# mcu.net
KiCad netlist of a schematic drawn in Altium Designer
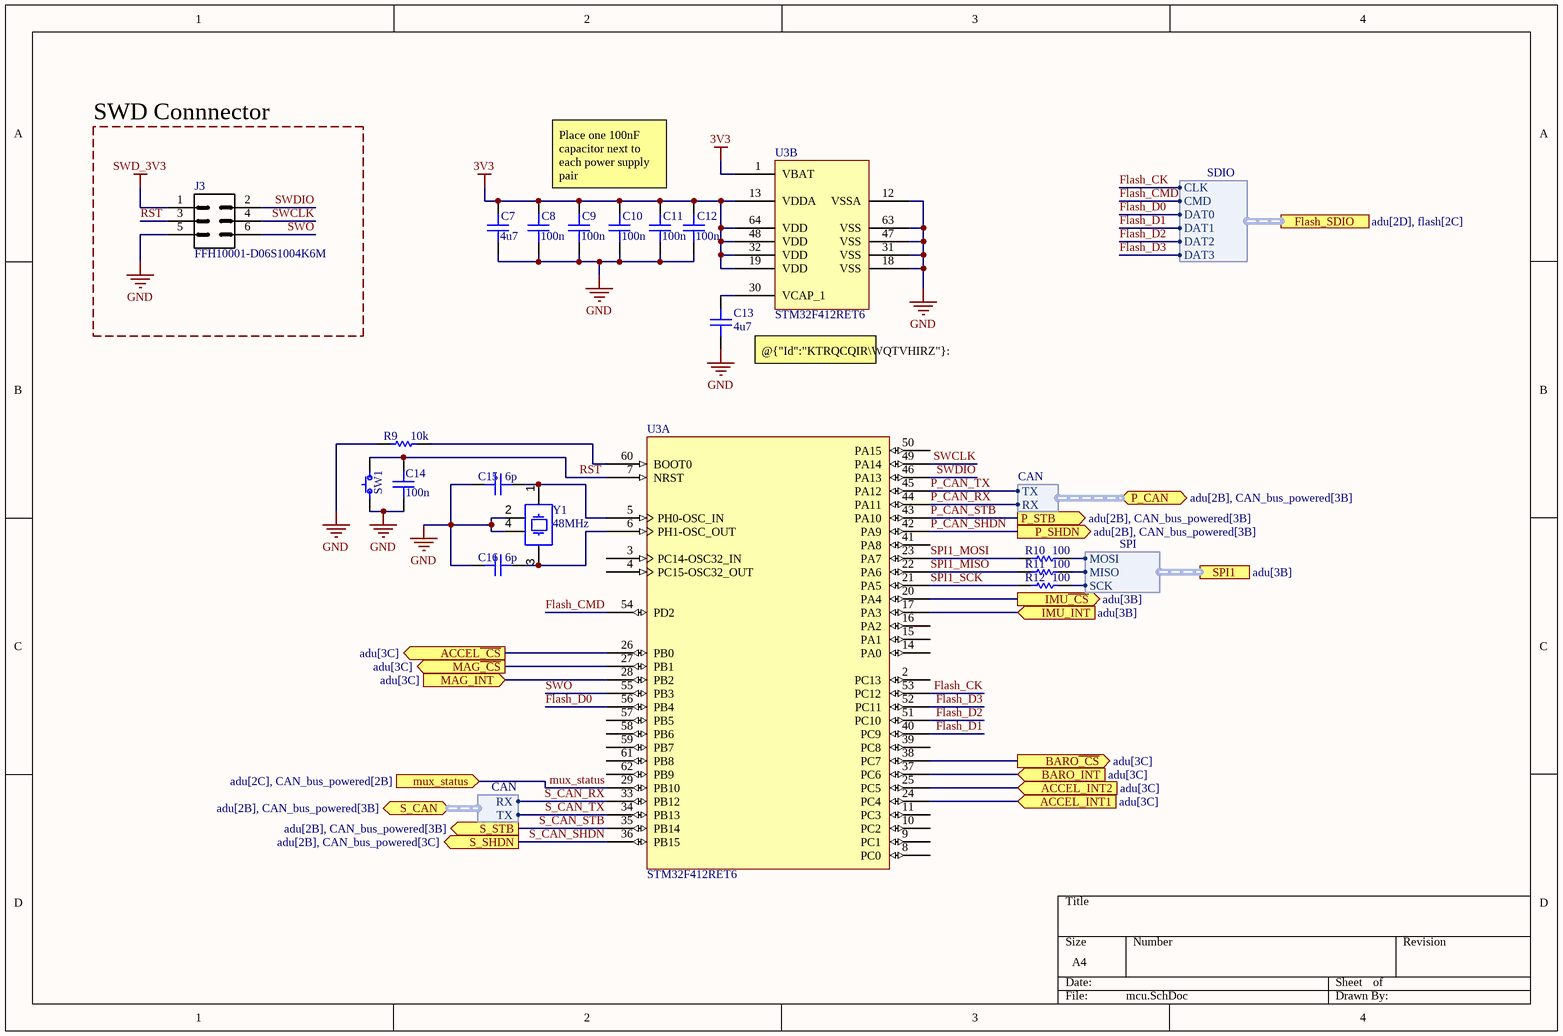
[diagram p0: mcu.SchDoc]

(export (version "E")
  (design (tool "Eeschema 10.0.6"))
  (components
    (comp (ref "C7")
      (value "4u7")
      (footprint "CAP-0603-NP")
      (description "Capacitor")
      (libsource (lib "drfc_schlib") (part "Capacitor"))
    )
    (comp (ref "C8")
      (value "100n")
      (footprint "CAP-0603-NP")
      (description "Capacitor")
      (libsource (lib "drfc_schlib") (part "Capacitor"))
    )
    (comp (ref "C9")
      (value "100n")
      (footprint "CAP-0603-NP")
      (description "Capacitor")
      (libsource (lib "drfc_schlib") (part "Capacitor"))
    )
    (comp (ref "C10")
      (value "100n")
      (footprint "CAP-0603-NP")
      (description "Capacitor")
      (libsource (lib "drfc_schlib") (part "Capacitor"))
    )
    (comp (ref "C11")
      (value "100n")
      (footprint "CAP-0603-NP")
      (description "Capacitor")
      (libsource (lib "drfc_schlib") (part "Capacitor"))
    )
    (comp (ref "C12")
      (value "100n")
      (footprint "CAP-0603-NP")
      (description "Capacitor")
      (libsource (lib "drfc_schlib") (part "Capacitor"))
    )
    (comp (ref "C13")
      (value "4u7")
      (footprint "CAP-0603-NP")
      (description "Capacitor")
      (libsource (lib "drfc_schlib") (part "Capacitor"))
    )
    (comp (ref "C14")
      (value "100n")
      (footprint "CAP-0603-NP")
      (description "Capacitor")
      (libsource (lib "drfc_schlib") (part "Capacitor"))
    )
    (comp (ref "C15")
      (value "6p")
      (footprint "CAP-0603-NP")
      (description "Capacitor")
      (libsource (lib "drfc_schlib") (part "Capacitor"))
    )
    (comp (ref "C16")
      (value "6p")
      (footprint "CAP-0603-NP")
      (description "Capacitor")
      (libsource (lib "drfc_schlib") (part "Capacitor"))
    )
    (comp (ref "J3")
      (value "FFH10001-D06S1004K6M")
      (footprint "SOP127P600-8N")
      (description "Connector 6-Pin 2 Row")
      (libsource (lib "drfc_schlib") (part "Connector 6-Pin 2 Row"))
    )
    (comp (ref "R9")
      (value "10k")
      (footprint "RES-0603")
      (description "Resistor")
      (libsource (lib "drfc_schlib") (part "Resistor"))
    )
    (comp (ref "R10")
      (value "100")
      (footprint "RES-0603")
      (description "Resistor")
      (libsource (lib "drfc_schlib") (part "Resistor"))
    )
    (comp (ref "R11")
      (value "100")
      (footprint "RES-0603")
      (description "Resistor")
      (libsource (lib "drfc_schlib") (part "Resistor"))
    )
    (comp (ref "R12")
      (value "100")
      (footprint "RES-0603")
      (description "Resistor")
      (libsource (lib "drfc_schlib") (part "Resistor"))
    )
    (comp (ref "SW1")
      (value "SPST Switch")
      (footprint "HYP 1TS026A-1000-0550-CT")
      (description "HYP (Hongyuan Precision) 1TS026A-1000-0550-CT")
      (libsource (lib "drfc_schlib") (part "SW_SPST"))
    )
    (comp (ref "U3")
      (value "STM32F412RET6")
      (footprint "STM32 LQFP64")
      (libsource (lib "drfc_schlib") (part "STM32F412RET6"))
    )
    (comp (ref "Y1")
      (value "48MHz")
      (footprint "XTAL_3.2x2.5mm")
      (description "HCI XC32M4-48.000-F08NLDT\r\n8pF load capacitance")
      (libsource (lib "drfc_schlib") (part "XTAL-4Pin"))
    )
  )
  (nets
    (net (code "4") (name "/ACCEL_INT1") (class "Default")
      (node (ref "U3") (pin "24") (pinfunction "PC4_24") (pintype "bidirectional"))
    )
    (net (code "5") (name "/ACCEL_INT2") (class "Default")
      (node (ref "U3") (pin "25") (pinfunction "PC5_25") (pintype "bidirectional"))
    )
    (net (code "6") (name "/ACCEL~{_CS}") (class "Default")
      (node (ref "U3") (pin "26") (pinfunction "PB0_26") (pintype "bidirectional"))
    )
    (net (code "7") (name "/BARO_INT") (class "Default")
      (node (ref "U3") (pin "37") (pinfunction "PC6_37") (pintype "bidirectional"))
    )
    (net (code "8") (name "/BARO~{_CS}") (class "Default")
      (node (ref "U3") (pin "38") (pinfunction "PC7_38") (pintype "bidirectional"))
    )
    (net (code "9") (name "/Flash_CK") (class "Default")
      (node (ref "U3") (pin "53") (pinfunction "PC12_53") (pintype "bidirectional"))
    )
    (net (code "10") (name "/Flash_CMD") (class "Default")
      (node (ref "U3") (pin "54") (pinfunction "PD2_54") (pintype "bidirectional"))
    )
    (net (code "11") (name "/Flash_D0") (class "Default")
      (node (ref "U3") (pin "56") (pinfunction "PB4_56") (pintype "bidirectional"))
    )
    (net (code "12") (name "/Flash_D1") (class "Default")
      (node (ref "U3") (pin "40") (pinfunction "PC9_40") (pintype "bidirectional"))
    )
    (net (code "13") (name "/Flash_D2") (class "Default")
      (node (ref "U3") (pin "51") (pinfunction "PC10_51") (pintype "bidirectional"))
    )
    (net (code "14") (name "/Flash_D3") (class "Default")
      (node (ref "U3") (pin "52") (pinfunction "PC11_52") (pintype "bidirectional"))
    )
    (net (code "15") (name "/IMU_INT") (class "Default")
      (node (ref "U3") (pin "17") (pinfunction "PA3_17") (pintype "bidirectional"))
    )
    (net (code "16") (name "/IMU~{_CS}") (class "Default")
      (node (ref "U3") (pin "20") (pinfunction "PA4_20") (pintype "bidirectional"))
    )
    (net (code "17") (name "/MAG_INT") (class "Default")
      (node (ref "U3") (pin "28") (pinfunction "PB2_28") (pintype "bidirectional"))
    )
    (net (code "18") (name "/MAG~{_CS}") (class "Default")
      (node (ref "U3") (pin "27") (pinfunction "PB1_27") (pintype "bidirectional"))
    )
    (net (code "19") (name "/MISO") (class "Default")
      (node (ref "R11") (pin "1") (pinfunction "1_1") (pintype "passive"))
    )
    (net (code "20") (name "/MOSI") (class "Default")
      (node (ref "R10") (pin "1") (pinfunction "1_1") (pintype "passive"))
    )
    (net (code "21") (name "/P_CAN_RX") (class "Default")
      (node (ref "U3") (pin "44") (pinfunction "PA11_44") (pintype "bidirectional"))
    )
    (net (code "22") (name "/P_CAN_SHDN") (class "Default")
      (node (ref "U3") (pin "42") (pinfunction "PA9_42") (pintype "bidirectional"))
    )
    (net (code "23") (name "/P_CAN_STB") (class "Default")
      (node (ref "U3") (pin "43") (pinfunction "PA10_43") (pintype "bidirectional"))
    )
    (net (code "24") (name "/P_CAN_TX") (class "Default")
      (node (ref "U3") (pin "45") (pinfunction "PA12_45") (pintype "bidirectional"))
    )
    (net (code "25") (name "/RST") (class "Default")
      (node (ref "C14") (pin "2") (pinfunction "2_2") (pintype "passive"))
      (node (ref "J3") (pin "3") (pinfunction "3_3") (pintype "passive"))
      (node (ref "SW1") (pin "2") (pinfunction "2_2") (pintype "passive"))
      (node (ref "U3") (pin "7") (pinfunction "NRST_7") (pintype "input"))
    )
    (net (code "26") (name "/SCK") (class "Default")
      (node (ref "R12") (pin "1") (pinfunction "1_1") (pintype "passive"))
    )
    (net (code "27") (name "/SPI1_MISO") (class "Default")
      (node (ref "R11") (pin "2") (pinfunction "2_2") (pintype "passive"))
      (node (ref "U3") (pin "22") (pinfunction "PA6_22") (pintype "bidirectional"))
    )
    (net (code "28") (name "/SPI1_MOSI") (class "Default")
      (node (ref "R10") (pin "2") (pinfunction "2_2") (pintype "passive"))
      (node (ref "U3") (pin "23") (pinfunction "PA7_23") (pintype "bidirectional"))
    )
    (net (code "29") (name "/SPI1_SCK") (class "Default")
      (node (ref "R12") (pin "2") (pinfunction "2_2") (pintype "passive"))
      (node (ref "U3") (pin "21") (pinfunction "PA5_21") (pintype "bidirectional"))
    )
    (net (code "30") (name "/SWCLK") (class "Default")
      (node (ref "J3") (pin "4") (pinfunction "4_4") (pintype "passive"))
      (node (ref "U3") (pin "49") (pinfunction "PA14_49") (pintype "bidirectional"))
    )
    (net (code "31") (name "/SWDIO") (class "Default")
      (node (ref "J3") (pin "2") (pinfunction "2_2") (pintype "passive"))
      (node (ref "U3") (pin "46") (pinfunction "PA13_46") (pintype "bidirectional"))
    )
    (net (code "32") (name "/SWO") (class "Default")
      (node (ref "J3") (pin "6") (pinfunction "3_6") (pintype "passive"))
      (node (ref "U3") (pin "55") (pinfunction "PB3_55") (pintype "bidirectional"))
    )
    (net (code "33") (name "/S_CAN_RX") (class "Default")
      (node (ref "U3") (pin "33") (pinfunction "PB12_33") (pintype "bidirectional"))
    )
    (net (code "34") (name "/S_CAN_SHDN") (class "Default")
      (node (ref "U3") (pin "36") (pinfunction "PB15_36") (pintype "bidirectional"))
    )
    (net (code "35") (name "/S_CAN_STB") (class "Default")
      (node (ref "U3") (pin "35") (pinfunction "PB14_35") (pintype "bidirectional"))
    )
    (net (code "36") (name "/S_CAN_TX") (class "Default")
      (node (ref "U3") (pin "34") (pinfunction "PB13_34") (pintype "bidirectional"))
    )
    (net (code "37") (name "/mux_status") (class "Default")
      (node (ref "U3") (pin "29") (pinfunction "PB10_29") (pintype "bidirectional"))
    )
    (net (code "41") (name "3V3") (class "Default")
      (node (ref "C10") (pin "2") (pinfunction "2_2") (pintype "passive"))
      (node (ref "C11") (pin "2") (pinfunction "2_2") (pintype "passive"))
      (node (ref "C12") (pin "2") (pinfunction "2_2") (pintype "passive"))
      (node (ref "C7") (pin "2") (pinfunction "2_2") (pintype "passive"))
      (node (ref "C8") (pin "2") (pinfunction "2_2") (pintype "passive"))
      (node (ref "C9") (pin "2") (pinfunction "2_2") (pintype "passive"))
      (node (ref "U3") (pin "1") (pinfunction "VBAT_1") (pintype "power_in"))
      (node (ref "U3") (pin "13") (pinfunction "VDDA_13") (pintype "power_in"))
      (node (ref "U3") (pin "19") (pinfunction "VDD_19") (pintype "power_in"))
      (node (ref "U3") (pin "32") (pinfunction "VDD_32") (pintype "power_in"))
      (node (ref "U3") (pin "48") (pinfunction "VDD_48") (pintype "power_in"))
      (node (ref "U3") (pin "64") (pinfunction "VDD_64") (pintype "power_in"))
    )
    (net (code "42") (name "GND") (class "Default")
      (node (ref "C10") (pin "1") (pinfunction "1_1") (pintype "passive"))
      (node (ref "C11") (pin "1") (pinfunction "1_1") (pintype "passive"))
      (node (ref "C12") (pin "1") (pinfunction "1_1") (pintype "passive"))
      (node (ref "C13") (pin "1") (pinfunction "1_1") (pintype "passive"))
      (node (ref "C14") (pin "1") (pinfunction "1_1") (pintype "passive"))
      (node (ref "C15") (pin "1") (pinfunction "1_1") (pintype "passive"))
      (node (ref "C16") (pin "1") (pinfunction "1_1") (pintype "passive"))
      (node (ref "C7") (pin "1") (pinfunction "1_1") (pintype "passive"))
      (node (ref "C8") (pin "1") (pinfunction "1_1") (pintype "passive"))
      (node (ref "C9") (pin "1") (pinfunction "1_1") (pintype "passive"))
      (node (ref "J3") (pin "5") (pinfunction "3_5") (pintype "passive"))
      (node (ref "R9") (pin "1") (pinfunction "1_1") (pintype "passive"))
      (node (ref "SW1") (pin "1") (pinfunction "1_1") (pintype "passive"))
      (node (ref "U3") (pin "12") (pinfunction "VSSA_12") (pintype "power_in"))
      (node (ref "U3") (pin "18") (pinfunction "VSS_18") (pintype "power_in"))
      (node (ref "U3") (pin "31") (pinfunction "VSS_31") (pintype "power_in"))
      (node (ref "U3") (pin "47") (pinfunction "VSS_47") (pintype "power_in"))
      (node (ref "U3") (pin "63") (pinfunction "VSS_63") (pintype "power_in"))
      (node (ref "Y1") (pin "2") (pinfunction "GND_2") (pintype "power_in"))
      (node (ref "Y1") (pin "4") (pinfunction "GND_4") (pintype "power_in"))
    )
    (net (code "43") (name "Net-(U3A-BOOT0)") (class "Default")
      (node (ref "R9") (pin "2") (pinfunction "2_2") (pintype "passive"))
      (node (ref "U3") (pin "60") (pinfunction "BOOT0_60") (pintype "input"))
    )
    (net (code "44") (name "Net-(U3A-PH0-OSC_IN)") (class "Default")
      (node (ref "C15") (pin "2") (pinfunction "2_2") (pintype "passive"))
      (node (ref "U3") (pin "5") (pinfunction "PH0-OSC_IN_5") (pintype "input"))
      (node (ref "Y1") (pin "1") (pinfunction "X1_1") (pintype "passive"))
    )
    (net (code "45") (name "Net-(U3A-PH1-OSC_OUT)") (class "Default")
      (node (ref "C16") (pin "2") (pinfunction "2_2") (pintype "passive"))
      (node (ref "U3") (pin "6") (pinfunction "PH1-OSC_OUT_6") (pintype "input"))
      (node (ref "Y1") (pin "3") (pinfunction "X2_3") (pintype "passive"))
    )
    (net (code "46") (name "Net-(U3B-VCAP_1)") (class "Default")
      (node (ref "C13") (pin "2") (pinfunction "2_2") (pintype "passive"))
      (node (ref "U3") (pin "30") (pinfunction "VCAP_1_30") (pintype "power_in"))
    )
    (net (code "47") (name "SWD_3V3") (class "Default")
      (node (ref "J3") (pin "1") (pinfunction "1_1") (pintype "passive"))
    )
    (net (code "48") (name "unconnected-(U3A-PA0-Pad14)") (class "Default")
      (node (ref "U3") (pin "14") (pinfunction "PA0_14") (pintype "bidirectional"))
    )
    (net (code "49") (name "unconnected-(U3A-PA1-Pad15)") (class "Default")
      (node (ref "U3") (pin "15") (pinfunction "PA1_15") (pintype "bidirectional"))
    )
    (net (code "50") (name "unconnected-(U3A-PA2-Pad16)") (class "Default")
      (node (ref "U3") (pin "16") (pinfunction "PA2_16") (pintype "bidirectional"))
    )
    (net (code "51") (name "unconnected-(U3A-PA8-Pad41)") (class "Default")
      (node (ref "U3") (pin "41") (pinfunction "PA8_41") (pintype "bidirectional"))
    )
    (net (code "52") (name "unconnected-(U3A-PA15-Pad50)") (class "Default")
      (node (ref "U3") (pin "50") (pinfunction "PA15_50") (pintype "bidirectional"))
    )
    (net (code "53") (name "unconnected-(U3A-PB5-Pad57)") (class "Default")
      (node (ref "U3") (pin "57") (pinfunction "PB5_57") (pintype "bidirectional"))
    )
    (net (code "54") (name "unconnected-(U3A-PB6-Pad58)") (class "Default")
      (node (ref "U3") (pin "58") (pinfunction "PB6_58") (pintype "bidirectional"))
    )
    (net (code "55") (name "unconnected-(U3A-PB7-Pad59)") (class "Default")
      (node (ref "U3") (pin "59") (pinfunction "PB7_59") (pintype "bidirectional"))
    )
    (net (code "56") (name "unconnected-(U3A-PB8-Pad61)") (class "Default")
      (node (ref "U3") (pin "61") (pinfunction "PB8_61") (pintype "bidirectional"))
    )
    (net (code "57") (name "unconnected-(U3A-PB9-Pad62)") (class "Default")
      (node (ref "U3") (pin "62") (pinfunction "PB9_62") (pintype "bidirectional"))
    )
    (net (code "58") (name "unconnected-(U3A-PC0-Pad8)") (class "Default")
      (node (ref "U3") (pin "8") (pinfunction "PC0_8") (pintype "bidirectional"))
    )
    (net (code "59") (name "unconnected-(U3A-PC1-Pad9)") (class "Default")
      (node (ref "U3") (pin "9") (pinfunction "PC1_9") (pintype "bidirectional"))
    )
    (net (code "60") (name "unconnected-(U3A-PC2-Pad10)") (class "Default")
      (node (ref "U3") (pin "10") (pinfunction "PC2_10") (pintype "bidirectional"))
    )
    (net (code "61") (name "unconnected-(U3A-PC3-Pad11)") (class "Default")
      (node (ref "U3") (pin "11") (pinfunction "PC3_11") (pintype "bidirectional"))
    )
    (net (code "62") (name "unconnected-(U3A-PC8-Pad39)") (class "Default")
      (node (ref "U3") (pin "39") (pinfunction "PC8_39") (pintype "bidirectional"))
    )
    (net (code "63") (name "unconnected-(U3A-PC13-Pad2)") (class "Default")
      (node (ref "U3") (pin "2") (pinfunction "PC13_2") (pintype "bidirectional"))
    )
    (net (code "64") (name "unconnected-(U3A-PC14-OSC32_IN-Pad3)") (class "Default")
      (node (ref "U3") (pin "3") (pinfunction "PC14-OSC32_IN_3") (pintype "input"))
    )
    (net (code "65") (name "unconnected-(U3A-PC15-OSC32_OUT-Pad4)") (class "Default")
      (node (ref "U3") (pin "4") (pinfunction "PC15-OSC32_OUT_4") (pintype "input"))
    )
  )
)
